# 4_Sensor_Boards.net
KiCad netlist of a schematic drawn in Altium Designer
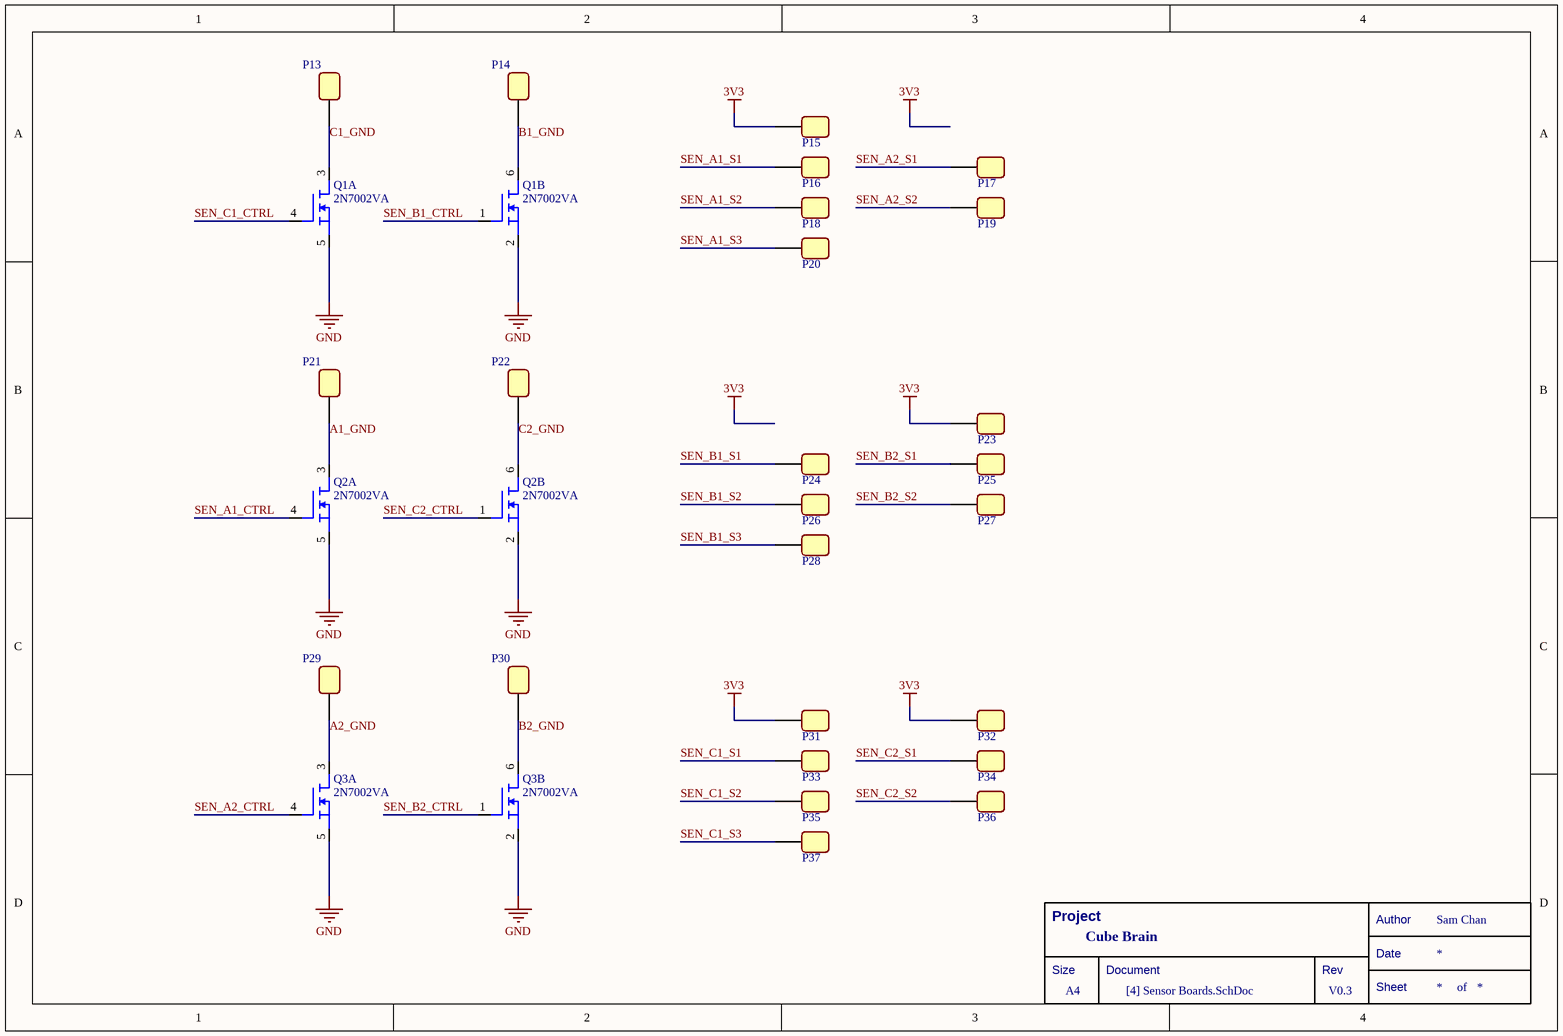
[diagram p0: [4] Sensor Boards.SchDoc]

(export (version "E")
  (design (tool "Eeschema 10.0.6"))
  (components
    (comp (ref "P13")
      (value "PAD_4")
      (footprint "PAD_0.5X1MM")
      (description "a Rec pad, 0.5X1mm")
      (libsource (lib "Cube Library") (part "PAD_4"))
    )
    (comp (ref "P14")
      (value "PAD_4")
      (footprint "PAD_0.5X1MM")
      (description "a Rec pad, 0.5X1mm")
      (libsource (lib "Cube Library") (part "PAD_4"))
    )
    (comp (ref "P15")
      (value "PAD_4")
      (footprint "PAD_0.5X1MM")
      (description "a Rec pad, 0.5X1mm")
      (libsource (lib "Cube Library") (part "PAD_4"))
    )
    (comp (ref "P16")
      (value "PAD_4")
      (footprint "PAD_0.5X1MM")
      (description "a Rec pad, 0.5X1mm")
      (libsource (lib "Cube Library") (part "PAD_4"))
    )
    (comp (ref "P17")
      (value "PAD_4")
      (footprint "PAD_0.5X1MM")
      (description "a Rec pad, 0.5X1mm")
      (libsource (lib "Cube Library") (part "PAD_4"))
    )
    (comp (ref "P18")
      (value "PAD_4")
      (footprint "PAD_0.5X1MM")
      (description "a Rec pad, 0.5X1mm")
      (libsource (lib "Cube Library") (part "PAD_4"))
    )
    (comp (ref "P19")
      (value "PAD_4")
      (footprint "PAD_0.5X1MM")
      (description "a Rec pad, 0.5X1mm")
      (libsource (lib "Cube Library") (part "PAD_4"))
    )
    (comp (ref "P20")
      (value "PAD_4")
      (footprint "PAD_0.5X1MM")
      (description "a Rec pad, 0.5X1mm")
      (libsource (lib "Cube Library") (part "PAD_4"))
    )
    (comp (ref "P21")
      (value "PAD_4")
      (footprint "PAD_0.5X1MM")
      (description "a Rec pad, 0.5X1mm")
      (libsource (lib "Cube Library") (part "PAD_4"))
    )
    (comp (ref "P22")
      (value "PAD_4")
      (footprint "PAD_0.5X1MM")
      (description "a Rec pad, 0.5X1mm")
      (libsource (lib "Cube Library") (part "PAD_4"))
    )
    (comp (ref "P23")
      (value "PAD_4")
      (footprint "PAD_0.5X1MM")
      (description "a Rec pad, 0.5X1mm")
      (libsource (lib "Cube Library") (part "PAD_4"))
    )
    (comp (ref "P24")
      (value "PAD_4")
      (footprint "PAD_0.5X1MM")
      (description "a Rec pad, 0.5X1mm")
      (libsource (lib "Cube Library") (part "PAD_4"))
    )
    (comp (ref "P25")
      (value "PAD_4")
      (footprint "PAD_0.5X1MM")
      (description "a Rec pad, 0.5X1mm")
      (libsource (lib "Cube Library") (part "PAD_4"))
    )
    (comp (ref "P26")
      (value "PAD_4")
      (footprint "PAD_0.5X1MM")
      (description "a Rec pad, 0.5X1mm")
      (libsource (lib "Cube Library") (part "PAD_4"))
    )
    (comp (ref "P27")
      (value "PAD_4")
      (footprint "PAD_0.5X1MM")
      (description "a Rec pad, 0.5X1mm")
      (libsource (lib "Cube Library") (part "PAD_4"))
    )
    (comp (ref "P28")
      (value "PAD_4")
      (footprint "PAD_0.5X1MM")
      (description "a Rec pad, 0.5X1mm")
      (libsource (lib "Cube Library") (part "PAD_4"))
    )
    (comp (ref "P29")
      (value "PAD_4")
      (footprint "PAD_0.5X1MM")
      (description "a Rec pad, 0.5X1mm")
      (libsource (lib "Cube Library") (part "PAD_4"))
    )
    (comp (ref "P30")
      (value "PAD_4")
      (footprint "PAD_0.5X1MM")
      (description "a Rec pad, 0.5X1mm")
      (libsource (lib "Cube Library") (part "PAD_4"))
    )
    (comp (ref "P31")
      (value "PAD_4")
      (footprint "PAD_0.5X1MM")
      (description "a Rec pad, 0.5X1mm")
      (libsource (lib "Cube Library") (part "PAD_4"))
    )
    (comp (ref "P32")
      (value "PAD_4")
      (footprint "PAD_0.5X1MM")
      (description "a Rec pad, 0.5X1mm")
      (libsource (lib "Cube Library") (part "PAD_4"))
    )
    (comp (ref "P33")
      (value "PAD_4")
      (footprint "PAD_0.5X1MM")
      (description "a Rec pad, 0.5X1mm")
      (libsource (lib "Cube Library") (part "PAD_4"))
    )
    (comp (ref "P34")
      (value "PAD_4")
      (footprint "PAD_0.5X1MM")
      (description "a Rec pad, 0.5X1mm")
      (libsource (lib "Cube Library") (part "PAD_4"))
    )
    (comp (ref "P35")
      (value "PAD_4")
      (footprint "PAD_0.5X1MM")
      (description "a Rec pad, 0.5X1mm")
      (libsource (lib "Cube Library") (part "PAD_4"))
    )
    (comp (ref "P36")
      (value "PAD_4")
      (footprint "PAD_0.5X1MM")
      (description "a Rec pad, 0.5X1mm")
      (libsource (lib "Cube Library") (part "PAD_4"))
    )
    (comp (ref "P37")
      (value "PAD_4")
      (footprint "PAD_0.5X1MM")
      (description "a Rec pad, 0.5X1mm")
      (libsource (lib "Cube Library") (part "PAD_4"))
    )
    (comp (ref "Q1")
      (value "2N7002VA")
      (footprint "2N7002VA")
      (description "Mosfet Array 2 N-Channel (Dual) 60V 280mA 150mW Surface Mount SOT-563")
      (fields
        (field (name "MANUFACTURER") "Diodes Incorporated")
        (field (name "MANUFACTURER PART NUMBER") "2N7002VA-7-F")
      )
      (libsource (lib "Cube Library") (part "2N7002VA"))
    )
    (comp (ref "Q2")
      (value "2N7002VA")
      (footprint "2N7002VA")
      (description "Mosfet Array 2 N-Channel (Dual) 60V 280mA 150mW Surface Mount SOT-563")
      (fields
        (field (name "MANUFACTURER") "Diodes Incorporated")
        (field (name "MANUFACTURER PART NUMBER") "2N7002VA-7-F")
      )
      (libsource (lib "Cube Library") (part "2N7002VA"))
    )
    (comp (ref "Q3")
      (value "2N7002VA")
      (footprint "2N7002VA")
      (description "Mosfet Array 2 N-Channel (Dual) 60V 280mA 150mW Surface Mount SOT-563")
      (fields
        (field (name "MANUFACTURER") "Diodes Incorporated")
        (field (name "MANUFACTURER PART NUMBER") "2N7002VA-7-F")
      )
      (libsource (lib "Cube Library") (part "2N7002VA"))
    )
  )
  (nets
    (net (code "1") (name "/A1_GND") (class "Default")
      (node (ref "P21") (pin "1") (pinfunction "1_1") (pintype "passive"))
      (node (ref "Q2") (pin "3") (pinfunction "D1_3") (pintype "passive"))
    )
    (net (code "2") (name "/A2_GND") (class "Default")
      (node (ref "P29") (pin "1") (pinfunction "1_1") (pintype "passive"))
      (node (ref "Q3") (pin "3") (pinfunction "D1_3") (pintype "passive"))
    )
    (net (code "3") (name "/B1_GND") (class "Default")
      (node (ref "P14") (pin "1") (pinfunction "1_1") (pintype "passive"))
      (node (ref "Q1") (pin "6") (pinfunction "D2_6") (pintype "passive"))
    )
    (net (code "4") (name "/B2_GND") (class "Default")
      (node (ref "P30") (pin "1") (pinfunction "1_1") (pintype "passive"))
      (node (ref "Q3") (pin "6") (pinfunction "D2_6") (pintype "passive"))
    )
    (net (code "5") (name "/C1_GND") (class "Default")
      (node (ref "P13") (pin "1") (pinfunction "1_1") (pintype "passive"))
      (node (ref "Q1") (pin "3") (pinfunction "D1_3") (pintype "passive"))
    )
    (net (code "6") (name "/C2_GND") (class "Default")
      (node (ref "P22") (pin "1") (pinfunction "1_1") (pintype "passive"))
      (node (ref "Q2") (pin "6") (pinfunction "D2_6") (pintype "passive"))
    )
    (net (code "7") (name "/SEN_A1_CTRL") (class "Default")
      (node (ref "Q2") (pin "4") (pinfunction "G1_4") (pintype "passive"))
    )
    (net (code "8") (name "/SEN_A1_S1") (class "Default")
      (node (ref "P16") (pin "1") (pinfunction "1_1") (pintype "passive"))
    )
    (net (code "9") (name "/SEN_A1_S2") (class "Default")
      (node (ref "P18") (pin "1") (pinfunction "1_1") (pintype "passive"))
    )
    (net (code "10") (name "/SEN_A1_S3") (class "Default")
      (node (ref "P20") (pin "1") (pinfunction "1_1") (pintype "passive"))
    )
    (net (code "11") (name "/SEN_A2_CTRL") (class "Default")
      (node (ref "Q3") (pin "4") (pinfunction "G1_4") (pintype "passive"))
    )
    (net (code "12") (name "/SEN_A2_S1") (class "Default")
      (node (ref "P17") (pin "1") (pinfunction "1_1") (pintype "passive"))
    )
    (net (code "13") (name "/SEN_A2_S2") (class "Default")
      (node (ref "P19") (pin "1") (pinfunction "1_1") (pintype "passive"))
    )
    (net (code "14") (name "/SEN_B1_CTRL") (class "Default")
      (node (ref "Q1") (pin "1") (pinfunction "G2_1") (pintype "passive"))
    )
    (net (code "15") (name "/SEN_B1_S1") (class "Default")
      (node (ref "P24") (pin "1") (pinfunction "1_1") (pintype "passive"))
    )
    (net (code "16") (name "/SEN_B1_S2") (class "Default")
      (node (ref "P26") (pin "1") (pinfunction "1_1") (pintype "passive"))
    )
    (net (code "17") (name "/SEN_B1_S3") (class "Default")
      (node (ref "P28") (pin "1") (pinfunction "1_1") (pintype "passive"))
    )
    (net (code "18") (name "/SEN_B2_CTRL") (class "Default")
      (node (ref "Q3") (pin "1") (pinfunction "G2_1") (pintype "passive"))
    )
    (net (code "19") (name "/SEN_B2_S1") (class "Default")
      (node (ref "P25") (pin "1") (pinfunction "1_1") (pintype "passive"))
    )
    (net (code "20") (name "/SEN_B2_S2") (class "Default")
      (node (ref "P27") (pin "1") (pinfunction "1_1") (pintype "passive"))
    )
    (net (code "21") (name "/SEN_C1_CTRL") (class "Default")
      (node (ref "Q1") (pin "4") (pinfunction "G1_4") (pintype "passive"))
    )
    (net (code "22") (name "/SEN_C1_S1") (class "Default")
      (node (ref "P33") (pin "1") (pinfunction "1_1") (pintype "passive"))
    )
    (net (code "23") (name "/SEN_C1_S2") (class "Default")
      (node (ref "P35") (pin "1") (pinfunction "1_1") (pintype "passive"))
    )
    (net (code "24") (name "/SEN_C1_S3") (class "Default")
      (node (ref "P37") (pin "1") (pinfunction "1_1") (pintype "passive"))
    )
    (net (code "25") (name "/SEN_C2_CTRL") (class "Default")
      (node (ref "Q2") (pin "1") (pinfunction "G2_1") (pintype "passive"))
    )
    (net (code "26") (name "/SEN_C2_S1") (class "Default")
      (node (ref "P34") (pin "1") (pinfunction "1_1") (pintype "passive"))
    )
    (net (code "27") (name "/SEN_C2_S2") (class "Default")
      (node (ref "P36") (pin "1") (pinfunction "1_1") (pintype "passive"))
    )
    (net (code "28") (name "3V3") (class "Default")
      (node (ref "P15") (pin "1") (pinfunction "1_1") (pintype "passive"))
      (node (ref "P23") (pin "1") (pinfunction "1_1") (pintype "passive"))
      (node (ref "P31") (pin "1") (pinfunction "1_1") (pintype "passive"))
      (node (ref "P32") (pin "1") (pinfunction "1_1") (pintype "passive"))
    )
    (net (code "29") (name "GND") (class "Default")
      (node (ref "Q1") (pin "2") (pinfunction "S2_2") (pintype "passive"))
      (node (ref "Q1") (pin "5") (pinfunction "S1_5") (pintype "passive"))
      (node (ref "Q2") (pin "2") (pinfunction "S2_2") (pintype "passive"))
      (node (ref "Q2") (pin "5") (pinfunction "S1_5") (pintype "passive"))
      (node (ref "Q3") (pin "2") (pinfunction "S2_2") (pintype "passive"))
      (node (ref "Q3") (pin "5") (pinfunction "S1_5") (pintype "passive"))
    )
  )
)
